# pcie-led-high.net
KiCad netlist of a schematic drawn in EAGLE
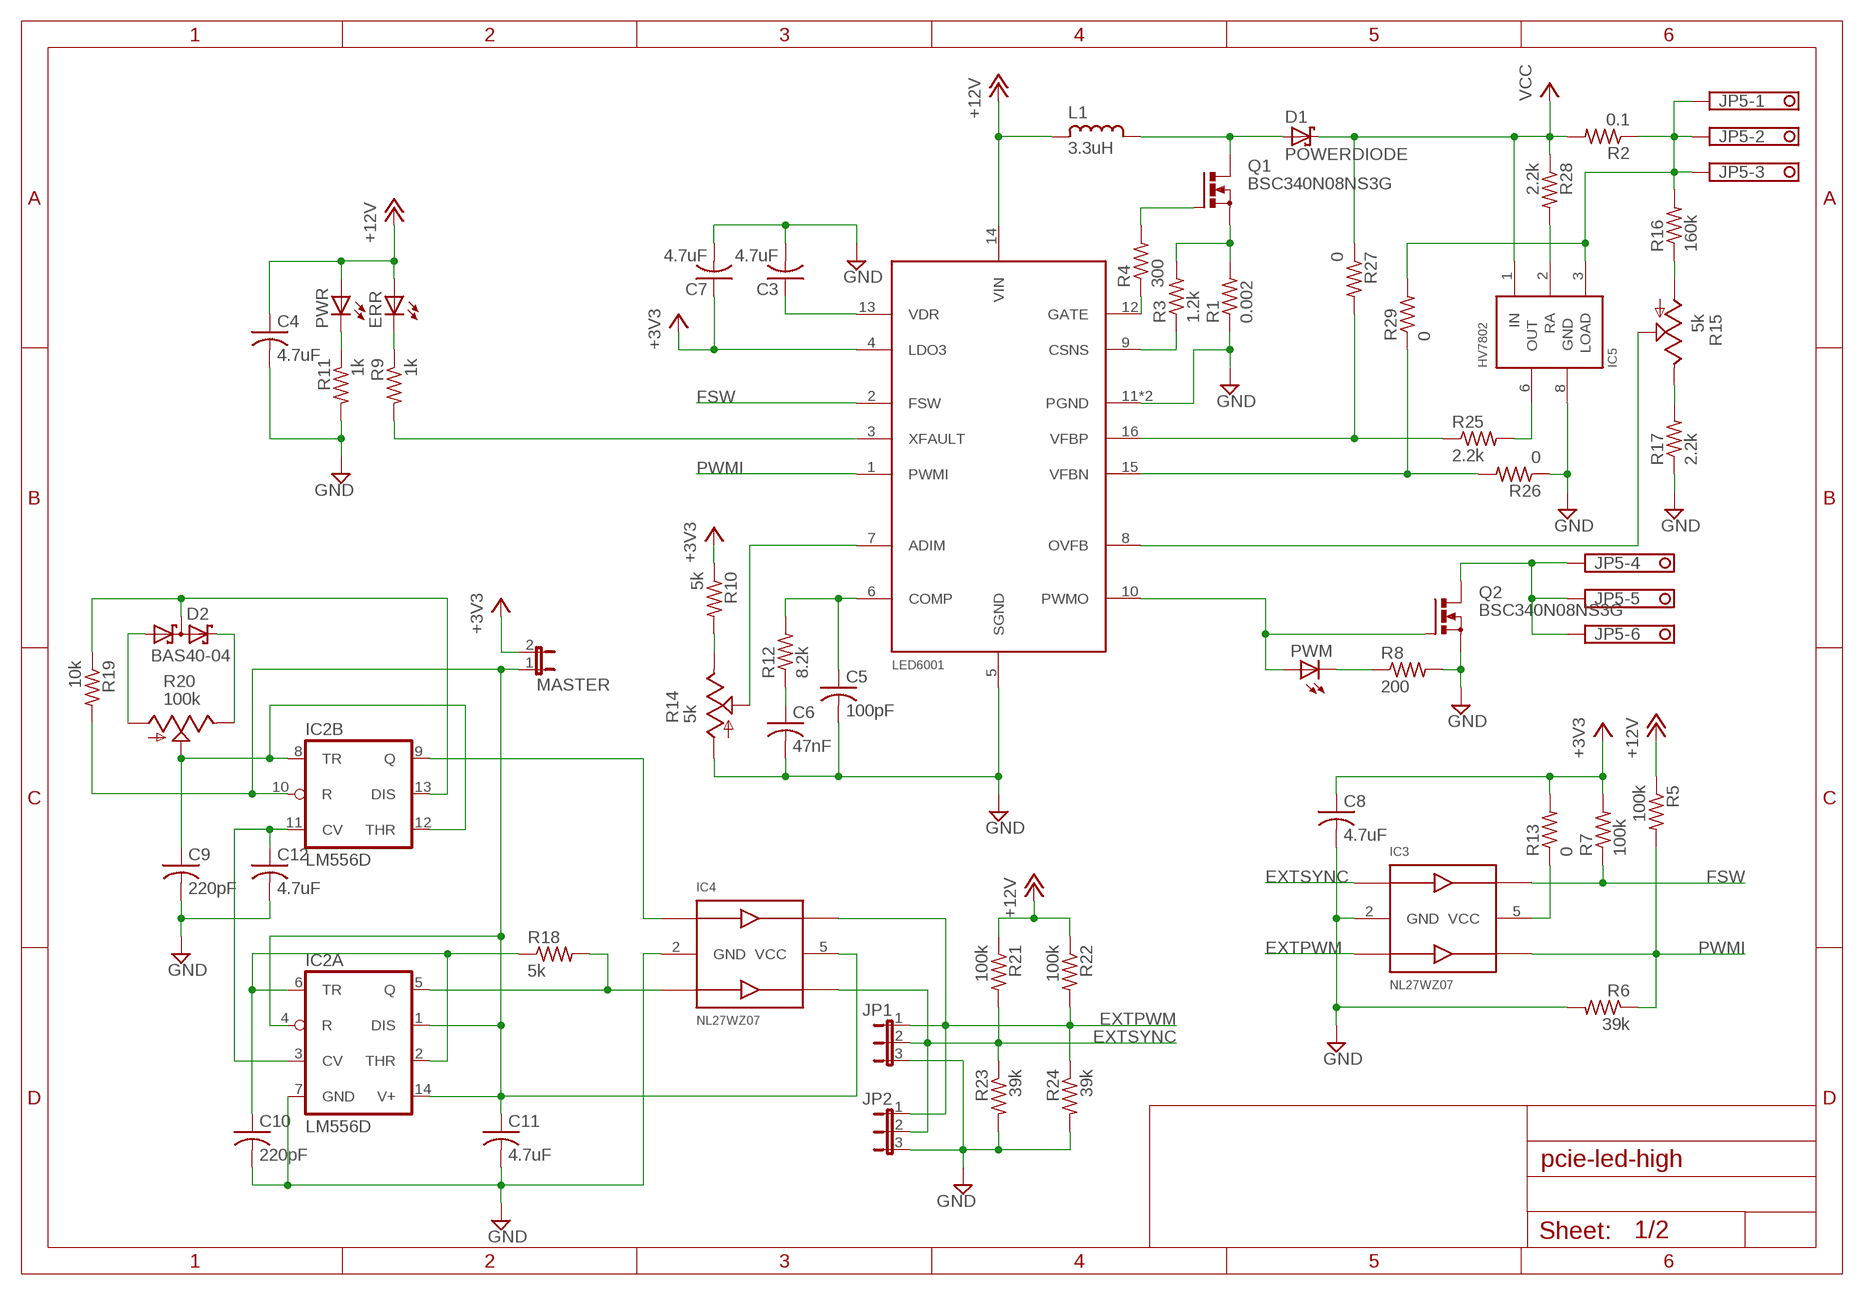
[diagram p0: schematic, sheet 1]
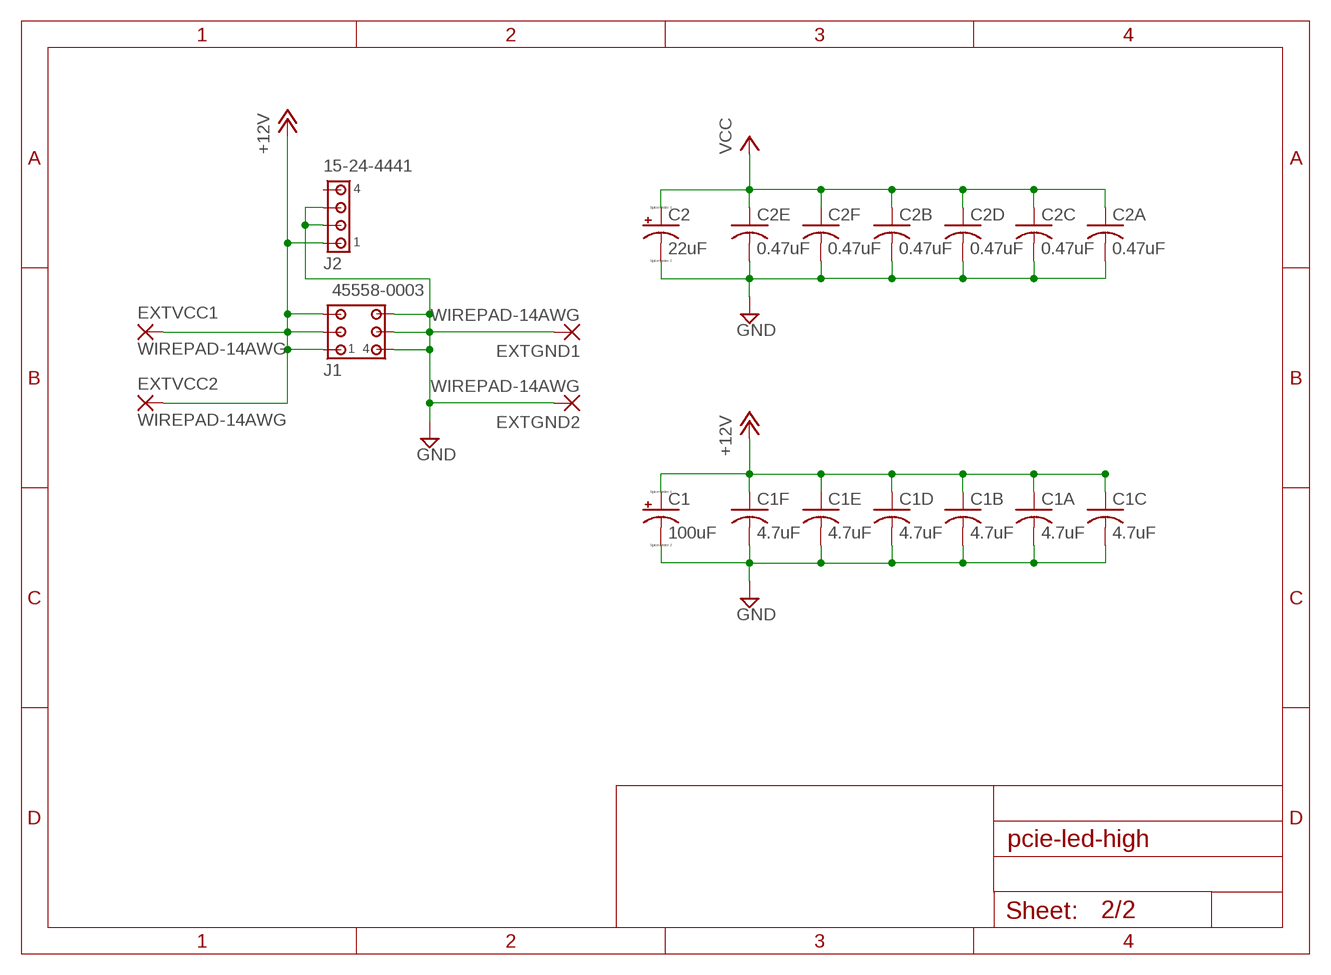
[diagram p1: schematic, sheet 2]

(export (version "E")
  (design (tool "Eeschema 10.0.6"))
  (components
    (comp (ref "C1")
      (value "100uF")
      (footprint "eagle-import:E3,5-8")
      (libsource (lib "eagle-import") (part "CPOL-USE3.5-8"))
    )
    (comp (ref "C1A")
      (value "4.7uF")
      (footprint "eagle-import:C0805")
      (libsource (lib "eagle-import") (part "C-USC0805"))
    )
    (comp (ref "C1B")
      (value "4.7uF")
      (footprint "eagle-import:C0805")
      (libsource (lib "eagle-import") (part "C-USC0805"))
    )
    (comp (ref "C1C")
      (value "4.7uF")
      (footprint "eagle-import:C0805")
      (libsource (lib "eagle-import") (part "C-USC0805"))
    )
    (comp (ref "C1D")
      (value "4.7uF")
      (footprint "eagle-import:C0805")
      (libsource (lib "eagle-import") (part "C-USC0805"))
    )
    (comp (ref "C1E")
      (value "4.7uF")
      (footprint "eagle-import:C0805")
      (libsource (lib "eagle-import") (part "C-USC0805"))
    )
    (comp (ref "C1F")
      (value "4.7uF")
      (footprint "eagle-import:C0805")
      (libsource (lib "eagle-import") (part "C-USC0805"))
    )
    (comp (ref "C2")
      (value "22uF")
      (footprint "eagle-import:E3,5-8")
      (libsource (lib "eagle-import") (part "CPOL-USE3.5-8"))
    )
    (comp (ref "C2A")
      (value "0.47uF")
      (footprint "eagle-import:C0805")
      (libsource (lib "eagle-import") (part "C-USC0805"))
    )
    (comp (ref "C2B")
      (value "0.47uF")
      (footprint "eagle-import:C0805")
      (libsource (lib "eagle-import") (part "C-USC0805"))
    )
    (comp (ref "C2C")
      (value "0.47uF")
      (footprint "eagle-import:C0805")
      (libsource (lib "eagle-import") (part "C-USC0805"))
    )
    (comp (ref "C2D")
      (value "0.47uF")
      (footprint "eagle-import:C0805")
      (libsource (lib "eagle-import") (part "C-USC0805"))
    )
    (comp (ref "C2E")
      (value "0.47uF")
      (footprint "eagle-import:C0805")
      (libsource (lib "eagle-import") (part "C-USC0805"))
    )
    (comp (ref "C2F")
      (value "0.47uF")
      (footprint "eagle-import:C0805")
      (libsource (lib "eagle-import") (part "C-USC0805"))
    )
    (comp (ref "EXTGND1")
      (value "WIREPAD-14AWG")
      (footprint "eagle-import:WIREPAD-14AWG")
      (libsource (lib "eagle-import") (part "WIREPAD-14AWG"))
    )
    (comp (ref "EXTGND2")
      (value "WIREPAD-14AWG")
      (footprint "eagle-import:WIREPAD-14AWG")
      (libsource (lib "eagle-import") (part "WIREPAD-14AWG"))
    )
    (comp (ref "EXTVCC1")
      (value "WIREPAD-14AWG")
      (footprint "eagle-import:WIREPAD-14AWG")
      (libsource (lib "eagle-import") (part "WIREPAD-14AWG"))
    )
    (comp (ref "EXTVCC2")
      (value "WIREPAD-14AWG")
      (footprint "eagle-import:WIREPAD-14AWG")
      (libsource (lib "eagle-import") (part "WIREPAD-14AWG"))
    )
    (comp (ref "J1")
      (value "45558-0003")
      (footprint "eagle-import:45558-0003")
      (libsource (lib "eagle-import") (part "45558-0003"))
    )
    (comp (ref "J2")
      (value "15-24-4441")
      (footprint "eagle-import:15-24-4441")
      (libsource (lib "eagle-import") (part "15-24-4441"))
    )
    (comp (ref "C3")
      (value "4.7uF")
      (footprint "eagle-import:C0603")
      (libsource (lib "eagle-import") (part "C-USC0603"))
    )
    (comp (ref "C4")
      (value "4.7uF")
      (footprint "eagle-import:C0603")
      (libsource (lib "eagle-import") (part "C-USC0603"))
    )
    (comp (ref "C5")
      (value "100pF")
      (footprint "eagle-import:C0603")
      (libsource (lib "eagle-import") (part "C-USC0603"))
    )
    (comp (ref "C6")
      (value "47nF")
      (footprint "eagle-import:C0603")
      (libsource (lib "eagle-import") (part "C-USC0603"))
    )
    (comp (ref "C7")
      (value "4.7uF")
      (footprint "eagle-import:C0603")
      (libsource (lib "eagle-import") (part "C-USC0603"))
    )
    (comp (ref "C8")
      (value "4.7uF")
      (footprint "eagle-import:C0603")
      (libsource (lib "eagle-import") (part "C-USC0603"))
    )
    (comp (ref "C9")
      (value "220pF")
      (footprint "eagle-import:C0603")
      (libsource (lib "eagle-import") (part "C-USC0603"))
    )
    (comp (ref "C10")
      (value "220pF")
      (footprint "eagle-import:C0603")
      (libsource (lib "eagle-import") (part "C-USC0603"))
    )
    (comp (ref "C11")
      (value "4.7uF")
      (footprint "eagle-import:C0603")
      (libsource (lib "eagle-import") (part "C-USC0603"))
    )
    (comp (ref "C12")
      (value "4.7uF")
      (footprint "eagle-import:C0603")
      (libsource (lib "eagle-import") (part "C-USC0603"))
    )
    (comp (ref "D1")
      (value "POWERDIODE")
      (footprint "eagle-import:LFPACK56-TO277")
      (libsource (lib "eagle-import") (part "POWERDIODE"))
    )
    (comp (ref "D2")
      (value "BAS40-04")
      (footprint "eagle-import:SOT23")
      (libsource (lib "eagle-import") (part "BAS40-04"))
    )
    (comp (ref "ERR")
      (value "LEDCHIP-LED0805")
      (footprint "eagle-import:CHIP-LED0805")
      (libsource (lib "eagle-import") (part "LEDCHIP-LED0805"))
    )
    (comp (ref "IC1")
      (value "LED6001")
      (footprint "eagle-import:HTSSOP-16")
      (libsource (lib "eagle-import") (part "LED6001"))
    )
    (comp (ref "IC2")
      (value "LM556D")
      (footprint "eagle-import:SO14")
      (libsource (lib "eagle-import") (part "556DLM"))
    )
    (comp (ref "IC3")
      (value "NL27WZ07")
      (footprint "eagle-import:SOT363")
      (libsource (lib "eagle-import") (part "NL27WZ07"))
    )
    (comp (ref "IC4")
      (value "NL27WZ07")
      (footprint "eagle-import:SOT363")
      (libsource (lib "eagle-import") (part "NL27WZ07"))
    )
    (comp (ref "IC5")
      (value "HV7802")
      (footprint "eagle-import:MSOP08")
      (libsource (lib "eagle-import") (part "HV7802"))
    )
    (comp (ref "JP1")
      (value "JP2E")
      (footprint "eagle-import:JP2")
      (libsource (lib "eagle-import") (part "JP2E"))
    )
    (comp (ref "JP2")
      (value "JP2E")
      (footprint "eagle-import:JP2")
      (libsource (lib "eagle-import") (part "JP2E"))
    )
    (comp (ref "JP5")
      (value "OSTTE06")
      (footprint "eagle-import:OSTTE06")
      (libsource (lib "eagle-import") (part "OSTTE06"))
    )
    (comp (ref "L1")
      (value "3.3uH")
      (footprint "eagle-import:SRP1770TA")
      (libsource (lib "eagle-import") (part "SRP1770TA"))
    )
    (comp (ref "MASTER")
      (value "JP1E")
      (footprint "eagle-import:JP1")
      (libsource (lib "eagle-import") (part "JP1E"))
    )
    (comp (ref "PWM")
      (value "LEDCHIP-LED0805")
      (footprint "eagle-import:CHIP-LED0805")
      (libsource (lib "eagle-import") (part "LEDCHIP-LED0805"))
    )
    (comp (ref "PWR")
      (value "LEDCHIP-LED0805")
      (footprint "eagle-import:CHIP-LED0805")
      (libsource (lib "eagle-import") (part "LEDCHIP-LED0805"))
    )
    (comp (ref "Q1")
      (value "BSC340N08NS3G")
      (footprint "eagle-import:PG-TDSON-8")
      (libsource (lib "eagle-import") (part "BSC340N08NS3G"))
    )
    (comp (ref "Q2")
      (value "BSC340N08NS3G")
      (footprint "eagle-import:PG-TDSON-8")
      (libsource (lib "eagle-import") (part "BSC340N08NS3G"))
    )
    (comp (ref "R1")
      (value "0.002")
      (footprint "eagle-import:R1206")
      (libsource (lib "eagle-import") (part "R-US_R1206"))
    )
    (comp (ref "R2")
      (value "0.1")
      (footprint "eagle-import:R2512")
      (libsource (lib "eagle-import") (part "R-US_R2512"))
    )
    (comp (ref "R3")
      (value "1.2k")
      (footprint "eagle-import:R0603")
      (libsource (lib "eagle-import") (part "R-US_R0603"))
    )
    (comp (ref "R4")
      (value "300")
      (footprint "eagle-import:R0603")
      (libsource (lib "eagle-import") (part "R-US_R0603"))
    )
    (comp (ref "R5")
      (value "100k")
      (footprint "eagle-import:R0603")
      (libsource (lib "eagle-import") (part "R-US_R0603"))
    )
    (comp (ref "R6")
      (value "39k")
      (footprint "eagle-import:R0603")
      (libsource (lib "eagle-import") (part "R-US_R0603"))
    )
    (comp (ref "R7")
      (value "100k")
      (footprint "eagle-import:R0603")
      (libsource (lib "eagle-import") (part "R-US_R0603"))
    )
    (comp (ref "R8")
      (value "200")
      (footprint "eagle-import:R0603")
      (libsource (lib "eagle-import") (part "R-US_R0603"))
    )
    (comp (ref "R9")
      (value "1k")
      (footprint "eagle-import:R0603")
      (libsource (lib "eagle-import") (part "R-US_R0603"))
    )
    (comp (ref "R10")
      (value "5k")
      (footprint "eagle-import:R0603")
      (libsource (lib "eagle-import") (part "R-US_R0603"))
    )
    (comp (ref "R11")
      (value "1k")
      (footprint "eagle-import:R0603")
      (libsource (lib "eagle-import") (part "R-US_R0603"))
    )
    (comp (ref "R12")
      (value "8.2k")
      (footprint "eagle-import:R0603")
      (libsource (lib "eagle-import") (part "R-US_R0603"))
    )
    (comp (ref "R13")
      (value "0")
      (footprint "eagle-import:R0603")
      (libsource (lib "eagle-import") (part "R-US_R0603"))
    )
    (comp (ref "R14")
      (value "5k")
      (footprint "eagle-import:ST-4EB")
      (libsource (lib "eagle-import") (part "ST4ETB"))
    )
    (comp (ref "R15")
      (value "5k")
      (footprint "eagle-import:ST-4EB")
      (libsource (lib "eagle-import") (part "ST4ETB"))
    )
    (comp (ref "R16")
      (value "160k")
      (footprint "eagle-import:R0603")
      (libsource (lib "eagle-import") (part "R-US_R0603"))
    )
    (comp (ref "R17")
      (value "2.2k")
      (footprint "eagle-import:R0603")
      (libsource (lib "eagle-import") (part "R-US_R0603"))
    )
    (comp (ref "R18")
      (value "5k")
      (footprint "eagle-import:R0603")
      (libsource (lib "eagle-import") (part "R-US_R0603"))
    )
    (comp (ref "R19")
      (value "10k")
      (footprint "eagle-import:R0603")
      (libsource (lib "eagle-import") (part "R-US_R0603"))
    )
    (comp (ref "R20")
      (value "100k")
      (footprint "eagle-import:P260T")
      (libsource (lib "eagle-import") (part "P260T"))
    )
    (comp (ref "R21")
      (value "100k")
      (footprint "eagle-import:R0603")
      (libsource (lib "eagle-import") (part "R-US_R0603"))
    )
    (comp (ref "R22")
      (value "100k")
      (footprint "eagle-import:R0603")
      (libsource (lib "eagle-import") (part "R-US_R0603"))
    )
    (comp (ref "R23")
      (value "39k")
      (footprint "eagle-import:R0603")
      (libsource (lib "eagle-import") (part "R-US_R0603"))
    )
    (comp (ref "R24")
      (value "39k")
      (footprint "eagle-import:R0603")
      (libsource (lib "eagle-import") (part "R-US_R0603"))
    )
    (comp (ref "R25")
      (value "2.2k")
      (footprint "eagle-import:R0603")
      (libsource (lib "eagle-import") (part "R-US_R0603"))
    )
    (comp (ref "R26")
      (value "0")
      (footprint "eagle-import:R0603")
      (libsource (lib "eagle-import") (part "R-US_R0603"))
    )
    (comp (ref "R27")
      (value "0")
      (footprint "eagle-import:R0603")
      (libsource (lib "eagle-import") (part "R-US_R0603"))
    )
    (comp (ref "R28")
      (value "2.2k")
      (footprint "eagle-import:R0603")
      (libsource (lib "eagle-import") (part "R-US_R0603"))
    )
    (comp (ref "R29")
      (value "0")
      (footprint "eagle-import:R0603")
      (libsource (lib "eagle-import") (part "R-US_R0603"))
    )
  )
  (nets
    (net (code "1") (name "+3V3") (class "Default")
      (node (ref "C7") (pin "1") (pinfunction "1_1") (pintype "passive"))
      (node (ref "C8") (pin "1") (pinfunction "1_1") (pintype "passive"))
      (node (ref "IC1") (pin "4") (pinfunction "LDO3_4") (pintype "bidirectional"))
      (node (ref "MASTER") (pin "2") (pinfunction "2_2") (pintype "passive"))
      (node (ref "R10") (pin "1") (pinfunction "1_1") (pintype "passive"))
      (node (ref "R13") (pin "2") (pinfunction "2_2") (pintype "passive"))
      (node (ref "R7") (pin "2") (pinfunction "2_2") (pintype "passive"))
    )
    (net (code "2") (name "+12V") (class "Default")
      (node (ref "C1") (pin "+") (pinfunction "+_+") (pintype "passive"))
      (node (ref "C1A") (pin "1") (pinfunction "1_1") (pintype "passive"))
      (node (ref "C1B") (pin "1") (pinfunction "1_1") (pintype "passive"))
      (node (ref "C1C") (pin "1") (pinfunction "1_1") (pintype "passive"))
      (node (ref "C1D") (pin "1") (pinfunction "1_1") (pintype "passive"))
      (node (ref "C1E") (pin "1") (pinfunction "1_1") (pintype "passive"))
      (node (ref "C1F") (pin "1") (pinfunction "1_1") (pintype "passive"))
      (node (ref "C4") (pin "1") (pinfunction "1_1") (pintype "passive"))
      (node (ref "ERR") (pin "A") (pinfunction "A_A") (pintype "passive"))
      (node (ref "EXTVCC1") (pin "TP") (pinfunction "P_TP") (pintype "passive"))
      (node (ref "EXTVCC2") (pin "TP") (pinfunction "P_TP") (pintype "passive"))
      (node (ref "IC1") (pin "14") (pinfunction "VIN_14") (pintype "bidirectional"))
      (node (ref "J1") (pin "1") (pinfunction "1_1") (pintype "passive"))
      (node (ref "J1") (pin "2") (pinfunction "2_2") (pintype "passive"))
      (node (ref "J1") (pin "3") (pinfunction "3_3") (pintype "passive"))
      (node (ref "J2") (pin "1") (pinfunction "1_1") (pintype "passive"))
      (node (ref "L1") (pin "P$1") (pinfunction "1_P$1") (pintype "passive"))
      (node (ref "PWR") (pin "A") (pinfunction "A_A") (pintype "passive"))
      (node (ref "R21") (pin "1") (pinfunction "1_1") (pintype "passive"))
      (node (ref "R22") (pin "1") (pinfunction "1_1") (pintype "passive"))
      (node (ref "R5") (pin "1") (pinfunction "1_1") (pintype "passive"))
    )
    (net (code "3") (name "EXTPWM") (class "Default")
      (node (ref "IC3") (pin "3") (pinfunction "IN2_3") (pintype "bidirectional"))
      (node (ref "IC4") (pin "6") (pinfunction "OUT1_6") (pintype "bidirectional"))
      (node (ref "JP1") (pin "1") (pinfunction "1_1") (pintype "passive"))
      (node (ref "JP2") (pin "1") (pinfunction "1_1") (pintype "passive"))
      (node (ref "R22") (pin "2") (pinfunction "2_2") (pintype "passive"))
      (node (ref "R24") (pin "1") (pinfunction "1_1") (pintype "passive"))
    )
    (net (code "4") (name "EXTSYNC") (class "Default")
      (node (ref "IC3") (pin "1") (pinfunction "IN1_1") (pintype "bidirectional"))
      (node (ref "IC4") (pin "4") (pinfunction "OUT2_4") (pintype "bidirectional"))
      (node (ref "JP1") (pin "2") (pinfunction "2_2") (pintype "passive"))
      (node (ref "JP2") (pin "2") (pinfunction "2_2") (pintype "passive"))
      (node (ref "R21") (pin "2") (pinfunction "2_2") (pintype "passive"))
      (node (ref "R23") (pin "1") (pinfunction "1_1") (pintype "passive"))
    )
    (net (code "5") (name "FSW") (class "Default")
      (node (ref "IC1") (pin "2") (pinfunction "FSW_2") (pintype "bidirectional"))
      (node (ref "IC3") (pin "6") (pinfunction "OUT1_6") (pintype "bidirectional"))
      (node (ref "R7") (pin "1") (pinfunction "1_1") (pintype "passive"))
    )
    (net (code "6") (name "GND") (class "Default")
      (node (ref "C1") (pin "-") (pinfunction "-_-") (pintype "passive"))
      (node (ref "C10") (pin "2") (pinfunction "2_2") (pintype "passive"))
      (node (ref "C11") (pin "2") (pinfunction "2_2") (pintype "passive"))
      (node (ref "C12") (pin "2") (pinfunction "2_2") (pintype "passive"))
      (node (ref "C1A") (pin "2") (pinfunction "2_2") (pintype "passive"))
      (node (ref "C1B") (pin "2") (pinfunction "2_2") (pintype "passive"))
      (node (ref "C1C") (pin "2") (pinfunction "2_2") (pintype "passive"))
      (node (ref "C1D") (pin "2") (pinfunction "2_2") (pintype "passive"))
      (node (ref "C1E") (pin "2") (pinfunction "2_2") (pintype "passive"))
      (node (ref "C1F") (pin "2") (pinfunction "2_2") (pintype "passive"))
      (node (ref "C2") (pin "-") (pinfunction "-_-") (pintype "passive"))
      (node (ref "C2A") (pin "2") (pinfunction "2_2") (pintype "passive"))
      (node (ref "C2B") (pin "2") (pinfunction "2_2") (pintype "passive"))
      (node (ref "C2C") (pin "2") (pinfunction "2_2") (pintype "passive"))
      (node (ref "C2D") (pin "2") (pinfunction "2_2") (pintype "passive"))
      (node (ref "C2E") (pin "2") (pinfunction "2_2") (pintype "passive"))
      (node (ref "C2F") (pin "2") (pinfunction "2_2") (pintype "passive"))
      (node (ref "C3") (pin "2") (pinfunction "2_2") (pintype "passive"))
      (node (ref "C4") (pin "2") (pinfunction "2_2") (pintype "passive"))
      (node (ref "C5") (pin "2") (pinfunction "2_2") (pintype "passive"))
      (node (ref "C6") (pin "2") (pinfunction "2_2") (pintype "passive"))
      (node (ref "C7") (pin "2") (pinfunction "2_2") (pintype "passive"))
      (node (ref "C8") (pin "2") (pinfunction "2_2") (pintype "passive"))
      (node (ref "C9") (pin "2") (pinfunction "2_2") (pintype "passive"))
      (node (ref "EXTGND1") (pin "TP") (pinfunction "P_TP") (pintype "passive"))
      (node (ref "EXTGND2") (pin "TP") (pinfunction "P_TP") (pintype "passive"))
      (node (ref "IC1") (pin "11") (pinfunction "PGND_11") (pintype "bidirectional"))
      (node (ref "IC1") (pin "5") (pinfunction "SGND_5") (pintype "bidirectional"))
      (node (ref "IC1") (pin "PAD") (pinfunction "PGND_PAD") (pintype "bidirectional"))
      (node (ref "IC2") (pin "7") (pinfunction "GND_7") (pintype "power_in"))
      (node (ref "IC3") (pin "2") (pinfunction "GND_2") (pintype "bidirectional"))
      (node (ref "IC4") (pin "2") (pinfunction "GND_2") (pintype "bidirectional"))
      (node (ref "IC5") (pin "8") (pinfunction "GND_8") (pintype "bidirectional"))
      (node (ref "J1") (pin "4") (pinfunction "4_4") (pintype "passive"))
      (node (ref "J1") (pin "5") (pinfunction "5_5") (pintype "passive"))
      (node (ref "J1") (pin "6") (pinfunction "6_6") (pintype "passive"))
      (node (ref "J2") (pin "2") (pinfunction "2_2") (pintype "passive"))
      (node (ref "J2") (pin "3") (pinfunction "3_3") (pintype "passive"))
      (node (ref "JP1") (pin "3") (pinfunction "3_3") (pintype "passive"))
      (node (ref "JP2") (pin "3") (pinfunction "3_3") (pintype "passive"))
      (node (ref "Q2") (pin "1") (pinfunction "S_1") (pintype "passive"))
      (node (ref "Q2") (pin "2") (pinfunction "S_2") (pintype "passive"))
      (node (ref "Q2") (pin "3") (pinfunction "S_3") (pintype "passive"))
      (node (ref "R1") (pin "1") (pinfunction "1_1") (pintype "passive"))
      (node (ref "R11") (pin "2") (pinfunction "2_2") (pintype "passive"))
      (node (ref "R14") (pin "1") (pinfunction "A_1") (pintype "passive"))
      (node (ref "R17") (pin "1") (pinfunction "1_1") (pintype "passive"))
      (node (ref "R23") (pin "2") (pinfunction "2_2") (pintype "passive"))
      (node (ref "R24") (pin "2") (pinfunction "2_2") (pintype "passive"))
      (node (ref "R26") (pin "1") (pinfunction "1_1") (pintype "passive"))
      (node (ref "R6") (pin "2") (pinfunction "2_2") (pintype "passive"))
      (node (ref "R8") (pin "2") (pinfunction "2_2") (pintype "passive"))
    )
    (net (code "7") (name "Net-(C6-Pad1)") (class "Default")
      (node (ref "C6") (pin "1") (pinfunction "1_1") (pintype "passive"))
      (node (ref "R12") (pin "1") (pinfunction "1_1") (pintype "passive"))
    )
    (net (code "8") (name "Net-(D2-A1)") (class "Default")
      (node (ref "D2") (pin "1") (pinfunction "A1_1") (pintype "passive"))
      (node (ref "R20") (pin "1") (pinfunction "A_1") (pintype "passive"))
    )
    (net (code "9") (name "Net-(D2-C1A2)") (class "Default")
      (node (ref "D2") (pin "3") (pinfunction "C1A2_3") (pintype "passive"))
      (node (ref "IC2") (pin "13") (pinfunction "DIS_13") (pintype "input"))
      (node (ref "R19") (pin "1") (pinfunction "1_1") (pintype "passive"))
    )
    (net (code "10") (name "Net-(D2-C2)") (class "Default")
      (node (ref "D2") (pin "2") (pinfunction "C2_2") (pintype "passive"))
      (node (ref "R20") (pin "3") (pinfunction "E_3") (pintype "passive"))
    )
    (net (code "11") (name "Net-(ERR-PadC)") (class "Default")
      (node (ref "ERR") (pin "C") (pinfunction "C_C") (pintype "passive"))
      (node (ref "R9") (pin "1") (pinfunction "1_1") (pintype "passive"))
    )
    (net (code "12") (name "Net-(IC1-ADIM)") (class "Default")
      (node (ref "IC1") (pin "7") (pinfunction "ADIM_7") (pintype "bidirectional"))
      (node (ref "R14") (pin "2") (pinfunction "S_2") (pintype "passive"))
    )
    (net (code "13") (name "Net-(IC1-COMP)") (class "Default")
      (node (ref "C5") (pin "1") (pinfunction "1_1") (pintype "passive"))
      (node (ref "IC1") (pin "6") (pinfunction "COMP_6") (pintype "bidirectional"))
      (node (ref "R12") (pin "2") (pinfunction "2_2") (pintype "passive"))
    )
    (net (code "14") (name "Net-(IC1-CSNS)") (class "Default")
      (node (ref "IC1") (pin "9") (pinfunction "CSNS_9") (pintype "bidirectional"))
      (node (ref "R3") (pin "1") (pinfunction "1_1") (pintype "passive"))
    )
    (net (code "15") (name "Net-(IC1-GATE)") (class "Default")
      (node (ref "IC1") (pin "12") (pinfunction "GATE_12") (pintype "bidirectional"))
      (node (ref "R4") (pin "1") (pinfunction "1_1") (pintype "passive"))
    )
    (net (code "16") (name "Net-(IC1-OVFB)") (class "Default")
      (node (ref "IC1") (pin "8") (pinfunction "OVFB_8") (pintype "bidirectional"))
      (node (ref "R15") (pin "2") (pinfunction "S_2") (pintype "passive"))
    )
    (net (code "17") (name "Net-(IC1-PWMO)") (class "Default")
      (node (ref "IC1") (pin "10") (pinfunction "PWMO_10") (pintype "bidirectional"))
      (node (ref "PWM") (pin "A") (pinfunction "A_A") (pintype "passive"))
      (node (ref "Q2") (pin "4") (pinfunction "G_4") (pintype "passive"))
    )
    (net (code "18") (name "Net-(IC1-VDR)") (class "Default")
      (node (ref "C3") (pin "1") (pinfunction "1_1") (pintype "passive"))
      (node (ref "IC1") (pin "13") (pinfunction "VDR_13") (pintype "bidirectional"))
    )
    (net (code "19") (name "Net-(IC1-VFBN)") (class "Default")
      (node (ref "IC1") (pin "15") (pinfunction "VFBN_15") (pintype "bidirectional"))
      (node (ref "R26") (pin "2") (pinfunction "2_2") (pintype "passive"))
      (node (ref "R29") (pin "1") (pinfunction "1_1") (pintype "passive"))
    )
    (net (code "20") (name "Net-(IC1-VFBP)") (class "Default")
      (node (ref "IC1") (pin "16") (pinfunction "VFBP_16") (pintype "bidirectional"))
      (node (ref "R25") (pin "1") (pinfunction "1_1") (pintype "passive"))
      (node (ref "R27") (pin "2") (pinfunction "2_2") (pintype "passive"))
    )
    (net (code "21") (name "Net-(IC1-XFAULT)") (class "Default")
      (node (ref "IC1") (pin "3") (pinfunction "XFAULT_3") (pintype "bidirectional"))
      (node (ref "R9") (pin "2") (pinfunction "2_2") (pintype "passive"))
    )
    (net (code "22") (name "Net-(IC2A-CV)") (class "Default")
      (node (ref "C12") (pin "1") (pinfunction "1_1") (pintype "passive"))
      (node (ref "IC2") (pin "11") (pinfunction "CV_11") (pintype "input"))
      (node (ref "IC2") (pin "3") (pinfunction "CV_3") (pintype "input"))
    )
    (net (code "23") (name "Net-(IC2A-DIS)") (class "Default")
      (node (ref "C11") (pin "1") (pinfunction "1_1") (pintype "passive"))
      (node (ref "IC2") (pin "1") (pinfunction "DIS_1") (pintype "input"))
      (node (ref "IC2") (pin "10") (pinfunction "R_10") (pintype "input"))
      (node (ref "IC2") (pin "14") (pinfunction "V+_14") (pintype "power_in"))
      (node (ref "IC2") (pin "4") (pinfunction "R_4") (pintype "input"))
      (node (ref "IC4") (pin "5") (pinfunction "VCC_5") (pintype "bidirectional"))
      (node (ref "MASTER") (pin "1") (pinfunction "1_1") (pintype "passive"))
      (node (ref "R19") (pin "2") (pinfunction "2_2") (pintype "passive"))
    )
    (net (code "24") (name "Net-(IC2A-Q)") (class "Default")
      (node (ref "IC2") (pin "5") (pinfunction "Q_5") (pintype "output"))
      (node (ref "IC4") (pin "3") (pinfunction "IN2_3") (pintype "bidirectional"))
      (node (ref "R18") (pin "2") (pinfunction "2_2") (pintype "passive"))
    )
    (net (code "25") (name "Net-(IC2A-THR)") (class "Default")
      (node (ref "C10") (pin "1") (pinfunction "1_1") (pintype "passive"))
      (node (ref "IC2") (pin "2") (pinfunction "THR_2") (pintype "input"))
      (node (ref "IC2") (pin "6") (pinfunction "TR_6") (pintype "input"))
      (node (ref "R18") (pin "1") (pinfunction "1_1") (pintype "passive"))
    )
    (net (code "26") (name "Net-(IC2B-Q)") (class "Default")
      (node (ref "IC2") (pin "9") (pinfunction "Q_9") (pintype "output"))
      (node (ref "IC4") (pin "1") (pinfunction "IN1_1") (pintype "bidirectional"))
    )
    (net (code "27") (name "Net-(IC2B-THR)") (class "Default")
      (node (ref "C9") (pin "1") (pinfunction "1_1") (pintype "passive"))
      (node (ref "IC2") (pin "12") (pinfunction "THR_12") (pintype "input"))
      (node (ref "IC2") (pin "8") (pinfunction "TR_8") (pintype "input"))
      (node (ref "R20") (pin "2") (pinfunction "S_2") (pintype "passive"))
    )
    (net (code "28") (name "Net-(IC3-VCC)") (class "Default")
      (node (ref "IC3") (pin "5") (pinfunction "VCC_5") (pintype "bidirectional"))
      (node (ref "R13") (pin "1") (pinfunction "1_1") (pintype "passive"))
    )
    (net (code "29") (name "Net-(IC5-LOAD)") (class "Default")
      (node (ref "IC5") (pin "3") (pinfunction "LOAD_3") (pintype "bidirectional"))
      (node (ref "JP5") (pin "1") (pinfunction "K_1") (pintype "passive"))
      (node (ref "JP5") (pin "2") (pinfunction "K_2") (pintype "passive"))
      (node (ref "JP5") (pin "3") (pinfunction "K_3") (pintype "passive"))
      (node (ref "R16") (pin "2") (pinfunction "2_2") (pintype "passive"))
      (node (ref "R2") (pin "1") (pinfunction "1_1") (pintype "passive"))
      (node (ref "R29") (pin "2") (pinfunction "2_2") (pintype "passive"))
    )
    (net (code "30") (name "Net-(IC5-OUT)") (class "Default")
      (node (ref "IC5") (pin "6") (pinfunction "OUT_6") (pintype "bidirectional"))
      (node (ref "R25") (pin "2") (pinfunction "2_2") (pintype "passive"))
    )
    (net (code "31") (name "Net-(IC5-RA)") (class "Default")
      (node (ref "IC5") (pin "2") (pinfunction "RA_2") (pintype "bidirectional"))
      (node (ref "R28") (pin "2") (pinfunction "2_2") (pintype "passive"))
    )
    (net (code "32") (name "Net-(JP5D-K)") (class "Default")
      (node (ref "JP5") (pin "4") (pinfunction "K_4") (pintype "passive"))
      (node (ref "JP5") (pin "5") (pinfunction "K_5") (pintype "passive"))
      (node (ref "JP5") (pin "6") (pinfunction "K_6") (pintype "passive"))
      (node (ref "Q2") (pin "5") (pinfunction "D_5") (pintype "passive"))
      (node (ref "Q2") (pin "6") (pinfunction "D_6") (pintype "passive"))
      (node (ref "Q2") (pin "7") (pinfunction "D_7") (pintype "passive"))
      (node (ref "Q2") (pin "8") (pinfunction "D_8") (pintype "passive"))
      (node (ref "Q2") (pin "TH") (pinfunction "D_TH") (pintype "passive"))
    )
    (net (code "33") (name "Net-(L1-4)") (class "Default")
      (node (ref "D1") (pin "A") (pinfunction "A_A") (pintype "passive"))
      (node (ref "L1") (pin "P$2") (pinfunction "4_P$2") (pintype "passive"))
      (node (ref "Q1") (pin "5") (pinfunction "D_5") (pintype "passive"))
      (node (ref "Q1") (pin "6") (pinfunction "D_6") (pintype "passive"))
      (node (ref "Q1") (pin "7") (pinfunction "D_7") (pintype "passive"))
      (node (ref "Q1") (pin "8") (pinfunction "D_8") (pintype "passive"))
      (node (ref "Q1") (pin "TH") (pinfunction "D_TH") (pintype "passive"))
    )
    (net (code "34") (name "Net-(PWM-PadC)") (class "Default")
      (node (ref "PWM") (pin "C") (pinfunction "C_C") (pintype "passive"))
      (node (ref "R8") (pin "1") (pinfunction "1_1") (pintype "passive"))
    )
    (net (code "35") (name "Net-(PWR-PadC)") (class "Default")
      (node (ref "PWR") (pin "C") (pinfunction "C_C") (pintype "passive"))
      (node (ref "R11") (pin "1") (pinfunction "1_1") (pintype "passive"))
    )
    (net (code "36") (name "Net-(Q1-G)") (class "Default")
      (node (ref "Q1") (pin "4") (pinfunction "G_4") (pintype "passive"))
      (node (ref "R4") (pin "2") (pinfunction "2_2") (pintype "passive"))
    )
    (net (code "37") (name "Net-(Q1-S-Pad1)") (class "Default")
      (node (ref "Q1") (pin "1") (pinfunction "S_1") (pintype "passive"))
      (node (ref "Q1") (pin "2") (pinfunction "S_2") (pintype "passive"))
      (node (ref "Q1") (pin "3") (pinfunction "S_3") (pintype "passive"))
      (node (ref "R1") (pin "2") (pinfunction "2_2") (pintype "passive"))
      (node (ref "R3") (pin "2") (pinfunction "2_2") (pintype "passive"))
    )
    (net (code "38") (name "Net-(R14-E)") (class "Default")
      (node (ref "R10") (pin "2") (pinfunction "2_2") (pintype "passive"))
      (node (ref "R14") (pin "3") (pinfunction "E_3") (pintype "passive"))
    )
    (net (code "39") (name "Net-(R15-A)") (class "Default")
      (node (ref "R15") (pin "1") (pinfunction "A_1") (pintype "passive"))
      (node (ref "R16") (pin "1") (pinfunction "1_1") (pintype "passive"))
    )
    (net (code "40") (name "Net-(R15-E)") (class "Default")
      (node (ref "R15") (pin "3") (pinfunction "E_3") (pintype "passive"))
      (node (ref "R17") (pin "2") (pinfunction "2_2") (pintype "passive"))
    )
    (net (code "41") (name "PWMI") (class "Default")
      (node (ref "IC1") (pin "1") (pinfunction "PWMI_1") (pintype "bidirectional"))
      (node (ref "IC3") (pin "4") (pinfunction "OUT2_4") (pintype "bidirectional"))
      (node (ref "R5") (pin "2") (pinfunction "2_2") (pintype "passive"))
      (node (ref "R6") (pin "1") (pinfunction "1_1") (pintype "passive"))
    )
    (net (code "42") (name "VCC") (class "Default")
      (node (ref "C2") (pin "+") (pinfunction "+_+") (pintype "passive"))
      (node (ref "C2A") (pin "1") (pinfunction "1_1") (pintype "passive"))
      (node (ref "C2B") (pin "1") (pinfunction "1_1") (pintype "passive"))
      (node (ref "C2C") (pin "1") (pinfunction "1_1") (pintype "passive"))
      (node (ref "C2D") (pin "1") (pinfunction "1_1") (pintype "passive"))
      (node (ref "C2E") (pin "1") (pinfunction "1_1") (pintype "passive"))
      (node (ref "C2F") (pin "1") (pinfunction "1_1") (pintype "passive"))
      (node (ref "D1") (pin "C1") (pinfunction "C_C1") (pintype "passive"))
      (node (ref "D1") (pin "C2") (pinfunction "C_C2") (pintype "passive"))
      (node (ref "D1") (pin "C3") (pinfunction "C_C3") (pintype "passive"))
      (node (ref "D1") (pin "C4") (pinfunction "C_C4") (pintype "passive"))
      (node (ref "D1") (pin "TH") (pinfunction "C_TH") (pintype "passive"))
      (node (ref "IC5") (pin "1") (pinfunction "IN_1") (pintype "bidirectional"))
      (node (ref "R2") (pin "2") (pinfunction "2_2") (pintype "passive"))
      (node (ref "R27") (pin "1") (pinfunction "1_1") (pintype "passive"))
      (node (ref "R28") (pin "1") (pinfunction "1_1") (pintype "passive"))
    )
    (net (code "43") (name "unconnected-(J2-Pad4)") (class "Default")
      (node (ref "J2") (pin "4") (pinfunction "4_4") (pintype "passive"))
    )
  )
)
